# Keyboard.net
KiCad netlist of a schematic drawn in Altium Designer
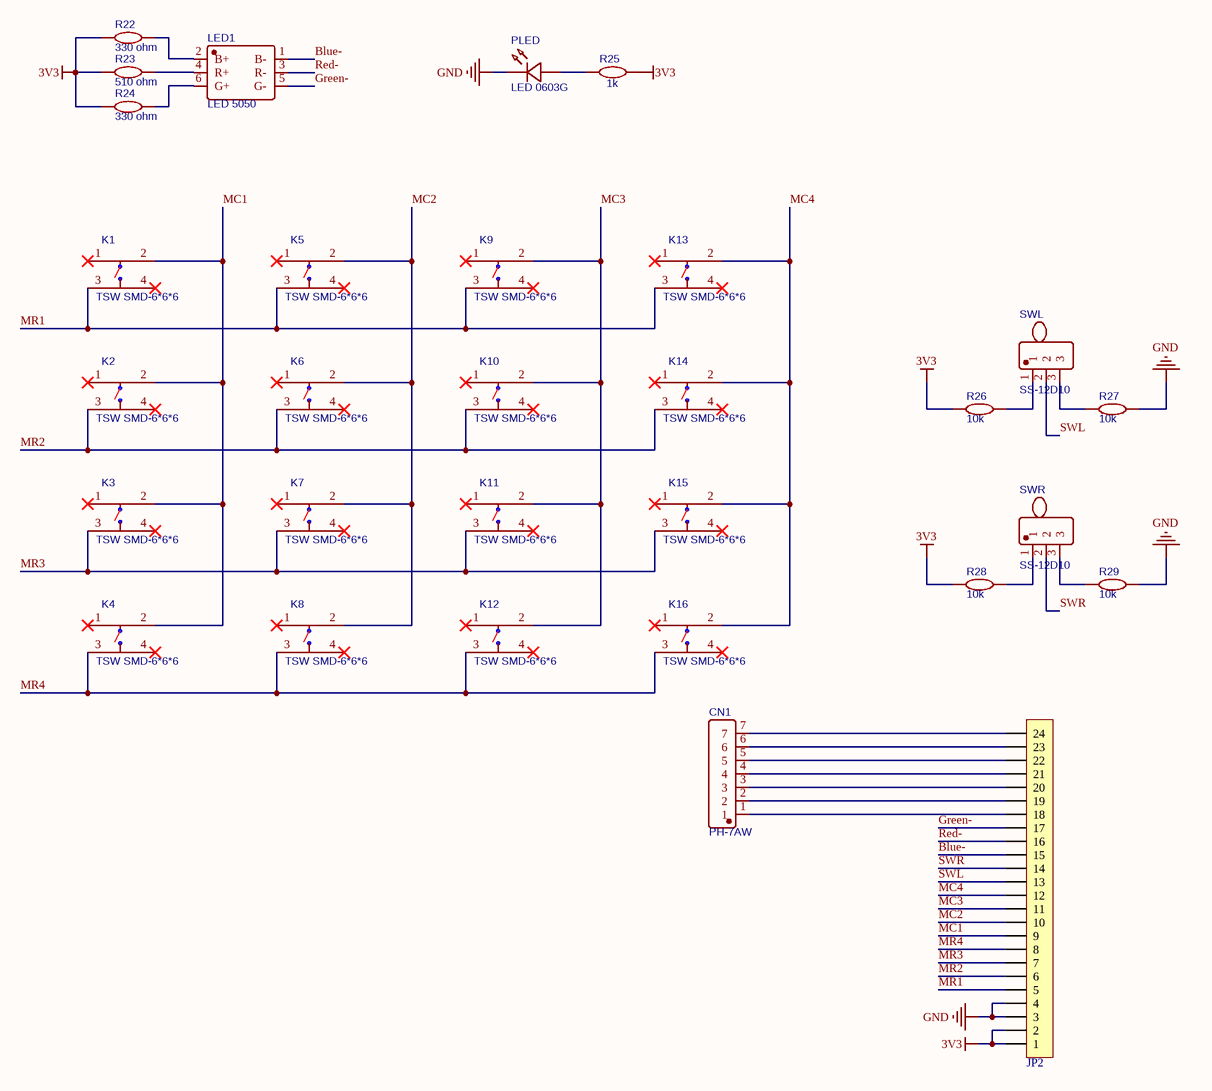
[diagram p0: Keyboard.SchDoc]

(export (version "E")
  (design (tool "Eeschema 10.0.6"))
  (components
    (comp (ref "CN1")
      (value "PH-7AW")
      (footprint "CONN-TH_PH-7AW")
      (fields (field (name "BOM_SUPPLIER PART") "C722789") (field (name "CONTRIBUTOR") "LCSC"))
      (libsource (lib "PH2.0_schlib") (part "PH-7AW"))
    )
    (comp (ref "JP2")
      (value "FPC1.0-24P")
      (footprint "FPC1.0-2H-WS-24P")
      (description "FPC连接器")
      (fields (field (name "版权归属") "黎明电子style"))
      (libsource (lib "FPC_schlib") (part "FPC-24P-1.0"))
    )
    (comp (ref "K1")
      (value "TSW SMD-6*6*6")
      (footprint "TSW SMD-6*6*6")
      (fields
        (field (name "BOM_SUPPLIER PART") "C231715")
        (field (name "BOM_MANUFACTURER PART") "KAN0661-1001B")
        (field (name "CONTRIBUTOR") "LCSC")
      )
      (libsource (lib "Button_schlib") (part "TSW SMD-6*6*6"))
    )
    (comp (ref "K2")
      (value "TSW SMD-6*6*6")
      (footprint "TSW SMD-6*6*6")
      (fields
        (field (name "BOM_SUPPLIER PART") "C231715")
        (field (name "BOM_MANUFACTURER PART") "KAN0661-1001B")
        (field (name "CONTRIBUTOR") "LCSC")
      )
      (libsource (lib "Button_schlib") (part "TSW SMD-6*6*6"))
    )
    (comp (ref "K3")
      (value "TSW SMD-6*6*6")
      (footprint "TSW SMD-6*6*6")
      (fields
        (field (name "BOM_SUPPLIER PART") "C231715")
        (field (name "BOM_MANUFACTURER PART") "KAN0661-1001B")
        (field (name "CONTRIBUTOR") "LCSC")
      )
      (libsource (lib "Button_schlib") (part "TSW SMD-6*6*6"))
    )
    (comp (ref "K4")
      (value "TSW SMD-6*6*6")
      (footprint "TSW SMD-6*6*6")
      (fields
        (field (name "BOM_SUPPLIER PART") "C231715")
        (field (name "BOM_MANUFACTURER PART") "KAN0661-1001B")
        (field (name "CONTRIBUTOR") "LCSC")
      )
      (libsource (lib "Button_schlib") (part "TSW SMD-6*6*6"))
    )
    (comp (ref "K5")
      (value "TSW SMD-6*6*6")
      (footprint "TSW SMD-6*6*6")
      (fields
        (field (name "BOM_SUPPLIER PART") "C231715")
        (field (name "BOM_MANUFACTURER PART") "KAN0661-1001B")
        (field (name "CONTRIBUTOR") "LCSC")
      )
      (libsource (lib "Button_schlib") (part "TSW SMD-6*6*6"))
    )
    (comp (ref "K6")
      (value "TSW SMD-6*6*6")
      (footprint "TSW SMD-6*6*6")
      (fields
        (field (name "BOM_SUPPLIER PART") "C231715")
        (field (name "BOM_MANUFACTURER PART") "KAN0661-1001B")
        (field (name "CONTRIBUTOR") "LCSC")
      )
      (libsource (lib "Button_schlib") (part "TSW SMD-6*6*6"))
    )
    (comp (ref "K7")
      (value "TSW SMD-6*6*6")
      (footprint "TSW SMD-6*6*6")
      (fields
        (field (name "BOM_SUPPLIER PART") "C231715")
        (field (name "BOM_MANUFACTURER PART") "KAN0661-1001B")
        (field (name "CONTRIBUTOR") "LCSC")
      )
      (libsource (lib "Button_schlib") (part "TSW SMD-6*6*6"))
    )
    (comp (ref "K8")
      (value "TSW SMD-6*6*6")
      (footprint "TSW SMD-6*6*6")
      (fields
        (field (name "BOM_SUPPLIER PART") "C231715")
        (field (name "BOM_MANUFACTURER PART") "KAN0661-1001B")
        (field (name "CONTRIBUTOR") "LCSC")
      )
      (libsource (lib "Button_schlib") (part "TSW SMD-6*6*6"))
    )
    (comp (ref "K9")
      (value "TSW SMD-6*6*6")
      (footprint "TSW SMD-6*6*6")
      (fields
        (field (name "BOM_SUPPLIER PART") "C231715")
        (field (name "BOM_MANUFACTURER PART") "KAN0661-1001B")
        (field (name "CONTRIBUTOR") "LCSC")
      )
      (libsource (lib "Button_schlib") (part "TSW SMD-6*6*6"))
    )
    (comp (ref "K10")
      (value "TSW SMD-6*6*6")
      (footprint "TSW SMD-6*6*6")
      (fields
        (field (name "BOM_SUPPLIER PART") "C231715")
        (field (name "BOM_MANUFACTURER PART") "KAN0661-1001B")
        (field (name "CONTRIBUTOR") "LCSC")
      )
      (libsource (lib "Button_schlib") (part "TSW SMD-6*6*6"))
    )
    (comp (ref "K11")
      (value "TSW SMD-6*6*6")
      (footprint "TSW SMD-6*6*6")
      (fields
        (field (name "BOM_SUPPLIER PART") "C231715")
        (field (name "BOM_MANUFACTURER PART") "KAN0661-1001B")
        (field (name "CONTRIBUTOR") "LCSC")
      )
      (libsource (lib "Button_schlib") (part "TSW SMD-6*6*6"))
    )
    (comp (ref "K12")
      (value "TSW SMD-6*6*6")
      (footprint "TSW SMD-6*6*6")
      (fields
        (field (name "BOM_SUPPLIER PART") "C231715")
        (field (name "BOM_MANUFACTURER PART") "KAN0661-1001B")
        (field (name "CONTRIBUTOR") "LCSC")
      )
      (libsource (lib "Button_schlib") (part "TSW SMD-6*6*6"))
    )
    (comp (ref "K13")
      (value "TSW SMD-6*6*6")
      (footprint "TSW SMD-6*6*6")
      (fields
        (field (name "BOM_SUPPLIER PART") "C231715")
        (field (name "BOM_MANUFACTURER PART") "KAN0661-1001B")
        (field (name "CONTRIBUTOR") "LCSC")
      )
      (libsource (lib "Button_schlib") (part "TSW SMD-6*6*6"))
    )
    (comp (ref "K14")
      (value "TSW SMD-6*6*6")
      (footprint "TSW SMD-6*6*6")
      (fields
        (field (name "BOM_SUPPLIER PART") "C231715")
        (field (name "BOM_MANUFACTURER PART") "KAN0661-1001B")
        (field (name "CONTRIBUTOR") "LCSC")
      )
      (libsource (lib "Button_schlib") (part "TSW SMD-6*6*6"))
    )
    (comp (ref "K15")
      (value "TSW SMD-6*6*6")
      (footprint "TSW SMD-6*6*6")
      (fields
        (field (name "BOM_SUPPLIER PART") "C231715")
        (field (name "BOM_MANUFACTURER PART") "KAN0661-1001B")
        (field (name "CONTRIBUTOR") "LCSC")
      )
      (libsource (lib "Button_schlib") (part "TSW SMD-6*6*6"))
    )
    (comp (ref "K16")
      (value "TSW SMD-6*6*6")
      (footprint "TSW SMD-6*6*6")
      (fields
        (field (name "BOM_SUPPLIER PART") "C231715")
        (field (name "BOM_MANUFACTURER PART") "KAN0661-1001B")
        (field (name "CONTRIBUTOR") "LCSC")
      )
      (libsource (lib "Button_schlib") (part "TSW SMD-6*6*6"))
    )
    (comp (ref "LED1")
      (value "LED 5050")
      (footprint "LED 5050")
      (description "5050RGB-LED")
      (fields
        (field (name "BOM_SUPPLIER PART") "C3014404")
        (field (name "BOM_MANUFACTURER PART") "11-21/BHC-AQ2S2/2T")
        (field (name "CONTRIBUTOR") "lcsc")
      )
      (libsource (lib "LED_schlib") (part "LED 5050"))
    )
    (comp (ref "PLED")
      (value "LED 0603G")
      (footprint "LED 0603G")
      (description "绿色0603LED")
      (fields
        (field (name "BOM_SUPPLIER PART") "C3014404")
        (field (name "BOM_MANUFACTURER PART") "11-21/BHC-AQ2S2/2T")
        (field (name "CONTRIBUTOR") "lcsc")
      )
      (libsource (lib "LED_schlib") (part "LED 0603G"))
    )
    (comp (ref "R22")
      (value "330 ohm")
      (footprint "R0603")
      (fields
        (field (name "BOM_SUPPLIER PART") "C326890")
        (field (name "BOM_MANUFACTURER PART") "SR0603JR-071RL")
        (field (name "CONTRIBUTOR") "LCSC")
      )
      (libsource (lib "RC_schlib") (part "R0603"))
    )
    (comp (ref "R23")
      (value "510 ohm")
      (footprint "R0603")
      (fields
        (field (name "BOM_SUPPLIER PART") "C326890")
        (field (name "BOM_MANUFACTURER PART") "SR0603JR-071RL")
        (field (name "CONTRIBUTOR") "LCSC")
      )
      (libsource (lib "RC_schlib") (part "R0603"))
    )
    (comp (ref "R24")
      (value "330 ohm")
      (footprint "R0603")
      (fields
        (field (name "BOM_SUPPLIER PART") "C326890")
        (field (name "BOM_MANUFACTURER PART") "SR0603JR-071RL")
        (field (name "CONTRIBUTOR") "LCSC")
      )
      (libsource (lib "RC_schlib") (part "R0603"))
    )
    (comp (ref "R25")
      (value "1k")
      (footprint "R0603")
      (fields
        (field (name "BOM_SUPPLIER PART") "C326890")
        (field (name "BOM_MANUFACTURER PART") "SR0603JR-071RL")
        (field (name "CONTRIBUTOR") "LCSC")
      )
      (libsource (lib "RC_schlib") (part "R0603"))
    )
    (comp (ref "R26")
      (value "10k")
      (footprint "R0603")
      (fields
        (field (name "BOM_SUPPLIER PART") "C326890")
        (field (name "BOM_MANUFACTURER PART") "SR0603JR-071RL")
        (field (name "CONTRIBUTOR") "LCSC")
      )
      (libsource (lib "RC_schlib") (part "R0603"))
    )
    (comp (ref "R27")
      (value "10k")
      (footprint "R0603")
      (fields
        (field (name "BOM_SUPPLIER PART") "C326890")
        (field (name "BOM_MANUFACTURER PART") "SR0603JR-071RL")
        (field (name "CONTRIBUTOR") "LCSC")
      )
      (libsource (lib "RC_schlib") (part "R0603"))
    )
    (comp (ref "R28")
      (value "10k")
      (footprint "R0603")
      (fields
        (field (name "BOM_SUPPLIER PART") "C326890")
        (field (name "BOM_MANUFACTURER PART") "SR0603JR-071RL")
        (field (name "CONTRIBUTOR") "LCSC")
      )
      (libsource (lib "RC_schlib") (part "R0603"))
    )
    (comp (ref "R29")
      (value "10k")
      (footprint "R0603")
      (fields
        (field (name "BOM_SUPPLIER PART") "C326890")
        (field (name "BOM_MANUFACTURER PART") "SR0603JR-071RL")
        (field (name "CONTRIBUTOR") "LCSC")
      )
      (libsource (lib "RC_schlib") (part "R0603"))
    )
    (comp (ref "SWL")
      (value "SS-12D10")
      (footprint "SS-12D10")
      (description "立式三脚拨动开关")
      (fields
        (field (name "BOM_SUPPLIER PART") "C496154")
        (field (name "BOM_MANUFACTURER PART") "1MS1T1B1M1QES-5")
        (field (name "CONTRIBUTOR") "LCSC")
      )
      (libsource (lib "Switch_schlib") (part "SS-12D10"))
    )
    (comp (ref "SWR")
      (value "SS-12D10")
      (footprint "SS-12D10")
      (description "立式三脚拨动开关")
      (fields
        (field (name "BOM_SUPPLIER PART") "C496154")
        (field (name "BOM_MANUFACTURER PART") "1MS1T1B1M1QES-5")
        (field (name "CONTRIBUTOR") "LCSC")
      )
      (libsource (lib "Switch_schlib") (part "SS-12D10"))
    )
  )
  (nets
    (net (code "1") (name "/Blue-") (class "Default")
      (node (ref "JP2") (pin "15") (pinfunction "15_15") (pintype "passive"))
      (node (ref "LED1") (pin "1") (pinfunction "B-_1") (pintype "passive"))
    )
    (net (code "2") (name "/Green-") (class "Default")
      (node (ref "JP2") (pin "17") (pinfunction "17_17") (pintype "passive"))
      (node (ref "LED1") (pin "5") (pinfunction "G-_5") (pintype "passive"))
    )
    (net (code "3") (name "/MC1") (class "Default")
      (node (ref "JP2") (pin "9") (pinfunction "9_9") (pintype "passive"))
      (node (ref "K1") (pin "2") (pinfunction "2_2") (pintype "passive"))
      (node (ref "K2") (pin "2") (pinfunction "2_2") (pintype "passive"))
      (node (ref "K3") (pin "2") (pinfunction "2_2") (pintype "passive"))
      (node (ref "K4") (pin "2") (pinfunction "2_2") (pintype "passive"))
    )
    (net (code "4") (name "/MC2") (class "Default")
      (node (ref "JP2") (pin "10") (pinfunction "10_10") (pintype "passive"))
      (node (ref "K5") (pin "2") (pinfunction "2_2") (pintype "passive"))
      (node (ref "K6") (pin "2") (pinfunction "2_2") (pintype "passive"))
      (node (ref "K7") (pin "2") (pinfunction "2_2") (pintype "passive"))
      (node (ref "K8") (pin "2") (pinfunction "2_2") (pintype "passive"))
    )
    (net (code "5") (name "/MC3") (class "Default")
      (node (ref "JP2") (pin "11") (pinfunction "11_11") (pintype "passive"))
      (node (ref "K10") (pin "2") (pinfunction "2_2") (pintype "passive"))
      (node (ref "K11") (pin "2") (pinfunction "2_2") (pintype "passive"))
      (node (ref "K12") (pin "2") (pinfunction "2_2") (pintype "passive"))
      (node (ref "K9") (pin "2") (pinfunction "2_2") (pintype "passive"))
    )
    (net (code "6") (name "/MC4") (class "Default")
      (node (ref "JP2") (pin "12") (pinfunction "12_12") (pintype "passive"))
      (node (ref "K13") (pin "2") (pinfunction "2_2") (pintype "passive"))
      (node (ref "K14") (pin "2") (pinfunction "2_2") (pintype "passive"))
      (node (ref "K15") (pin "2") (pinfunction "2_2") (pintype "passive"))
      (node (ref "K16") (pin "2") (pinfunction "2_2") (pintype "passive"))
    )
    (net (code "7") (name "/MR1") (class "Default")
      (node (ref "JP2") (pin "5") (pinfunction "5_5") (pintype "passive"))
      (node (ref "K1") (pin "3") (pinfunction "3_3") (pintype "passive"))
      (node (ref "K13") (pin "3") (pinfunction "3_3") (pintype "passive"))
      (node (ref "K5") (pin "3") (pinfunction "3_3") (pintype "passive"))
      (node (ref "K9") (pin "3") (pinfunction "3_3") (pintype "passive"))
    )
    (net (code "8") (name "/MR2") (class "Default")
      (node (ref "JP2") (pin "6") (pinfunction "6_6") (pintype "passive"))
      (node (ref "K10") (pin "3") (pinfunction "3_3") (pintype "passive"))
      (node (ref "K14") (pin "3") (pinfunction "3_3") (pintype "passive"))
      (node (ref "K2") (pin "3") (pinfunction "3_3") (pintype "passive"))
      (node (ref "K6") (pin "3") (pinfunction "3_3") (pintype "passive"))
    )
    (net (code "9") (name "/MR3") (class "Default")
      (node (ref "JP2") (pin "7") (pinfunction "7_7") (pintype "passive"))
      (node (ref "K11") (pin "3") (pinfunction "3_3") (pintype "passive"))
      (node (ref "K15") (pin "3") (pinfunction "3_3") (pintype "passive"))
      (node (ref "K3") (pin "3") (pinfunction "3_3") (pintype "passive"))
      (node (ref "K7") (pin "3") (pinfunction "3_3") (pintype "passive"))
    )
    (net (code "10") (name "/MR4") (class "Default")
      (node (ref "JP2") (pin "8") (pinfunction "8_8") (pintype "passive"))
      (node (ref "K12") (pin "3") (pinfunction "3_3") (pintype "passive"))
      (node (ref "K16") (pin "3") (pinfunction "3_3") (pintype "passive"))
      (node (ref "K4") (pin "3") (pinfunction "3_3") (pintype "passive"))
      (node (ref "K8") (pin "3") (pinfunction "3_3") (pintype "passive"))
    )
    (net (code "11") (name "/Red-") (class "Default")
      (node (ref "JP2") (pin "16") (pinfunction "16_16") (pintype "passive"))
      (node (ref "LED1") (pin "3") (pinfunction "R-_3") (pintype "passive"))
    )
    (net (code "12") (name "/SWL") (class "Default")
      (node (ref "JP2") (pin "13") (pinfunction "13_13") (pintype "passive"))
      (node (ref "SWL") (pin "2") (pinfunction "2_2") (pintype "passive"))
    )
    (net (code "13") (name "/SWR") (class "Default")
      (node (ref "JP2") (pin "14") (pinfunction "14_14") (pintype "passive"))
      (node (ref "SWR") (pin "2") (pinfunction "2_2") (pintype "passive"))
    )
    (net (code "14") (name "3V3") (class "Default")
      (node (ref "JP2") (pin "1") (pinfunction "1_1") (pintype "passive"))
      (node (ref "JP2") (pin "2") (pinfunction "2_2") (pintype "passive"))
      (node (ref "R22") (pin "2") (pinfunction "2_2") (pintype "passive"))
      (node (ref "R23") (pin "2") (pinfunction "2_2") (pintype "passive"))
      (node (ref "R24") (pin "2") (pinfunction "2_2") (pintype "passive"))
      (node (ref "R25") (pin "1") (pinfunction "1_1") (pintype "passive"))
      (node (ref "R26") (pin "1") (pinfunction "1_1") (pintype "passive"))
      (node (ref "R28") (pin "1") (pinfunction "1_1") (pintype "passive"))
    )
    (net (code "15") (name "GND") (class "Default")
      (node (ref "JP2") (pin "3") (pinfunction "3_3") (pintype "passive"))
      (node (ref "JP2") (pin "4") (pinfunction "4_4") (pintype "passive"))
      (node (ref "PLED") (pin "2") (pinfunction "K_2") (pintype "passive"))
      (node (ref "R27") (pin "2") (pinfunction "2_2") (pintype "passive"))
      (node (ref "R29") (pin "2") (pinfunction "2_2") (pintype "passive"))
    )
    (net (code "16") (name "Net-(CN1-Pad1)") (class "Default")
      (node (ref "CN1") (pin "1") (pinfunction "1_1") (pintype "passive"))
      (node (ref "JP2") (pin "18") (pinfunction "18_18") (pintype "passive"))
    )
    (net (code "17") (name "Net-(CN1-Pad2)") (class "Default")
      (node (ref "CN1") (pin "2") (pinfunction "2_2") (pintype "passive"))
      (node (ref "JP2") (pin "19") (pinfunction "19_19") (pintype "passive"))
    )
    (net (code "18") (name "Net-(CN1-Pad3)") (class "Default")
      (node (ref "CN1") (pin "3") (pinfunction "3_3") (pintype "passive"))
      (node (ref "JP2") (pin "20") (pinfunction "20_20") (pintype "passive"))
    )
    (net (code "19") (name "Net-(CN1-Pad4)") (class "Default")
      (node (ref "CN1") (pin "4") (pinfunction "4_4") (pintype "passive"))
      (node (ref "JP2") (pin "21") (pinfunction "21_21") (pintype "passive"))
    )
    (net (code "20") (name "Net-(CN1-Pad5)") (class "Default")
      (node (ref "CN1") (pin "5") (pinfunction "5_5") (pintype "passive"))
      (node (ref "JP2") (pin "22") (pinfunction "22_22") (pintype "passive"))
    )
    (net (code "21") (name "Net-(CN1-Pad6)") (class "Default")
      (node (ref "CN1") (pin "6") (pinfunction "6_6") (pintype "passive"))
      (node (ref "JP2") (pin "23") (pinfunction "23_23") (pintype "passive"))
    )
    (net (code "22") (name "Net-(CN1-Pad7)") (class "Default")
      (node (ref "CN1") (pin "7") (pinfunction "7_7") (pintype "passive"))
      (node (ref "JP2") (pin "24") (pinfunction "24_24") (pintype "passive"))
    )
    (net (code "23") (name "Net-(LED1-B+)") (class "Default")
      (node (ref "LED1") (pin "2") (pinfunction "B+_2") (pintype "passive"))
      (node (ref "R22") (pin "1") (pinfunction "1_1") (pintype "passive"))
    )
    (net (code "24") (name "Net-(LED1-G+)") (class "Default")
      (node (ref "LED1") (pin "6") (pinfunction "G+_6") (pintype "passive"))
      (node (ref "R24") (pin "1") (pinfunction "1_1") (pintype "passive"))
    )
    (net (code "25") (name "Net-(LED1-R+)") (class "Default")
      (node (ref "LED1") (pin "4") (pinfunction "R+_4") (pintype "passive"))
      (node (ref "R23") (pin "1") (pinfunction "1_1") (pintype "passive"))
    )
    (net (code "26") (name "Net-(PLED-A)") (class "Default")
      (node (ref "PLED") (pin "1") (pinfunction "A_1") (pintype "passive"))
      (node (ref "R25") (pin "2") (pinfunction "2_2") (pintype "passive"))
    )
    (net (code "27") (name "Net-(R26-Pad2)") (class "Default")
      (node (ref "R26") (pin "2") (pinfunction "2_2") (pintype "passive"))
      (node (ref "SWL") (pin "1") (pinfunction "1_1") (pintype "passive"))
    )
    (net (code "28") (name "Net-(R27-Pad1)") (class "Default")
      (node (ref "R27") (pin "1") (pinfunction "1_1") (pintype "passive"))
      (node (ref "SWL") (pin "3") (pinfunction "3_3") (pintype "passive"))
    )
    (net (code "29") (name "Net-(R28-Pad2)") (class "Default")
      (node (ref "R28") (pin "2") (pinfunction "2_2") (pintype "passive"))
      (node (ref "SWR") (pin "1") (pinfunction "1_1") (pintype "passive"))
    )
    (net (code "30") (name "Net-(R29-Pad1)") (class "Default")
      (node (ref "R29") (pin "1") (pinfunction "1_1") (pintype "passive"))
      (node (ref "SWR") (pin "3") (pinfunction "3_3") (pintype "passive"))
    )
    (net (code "31") (name "unconnected-(K1-Pad1)") (class "Default")
      (node (ref "K1") (pin "1") (pinfunction "1_1") (pintype "passive+no_connect"))
    )
    (net (code "32") (name "unconnected-(K1-Pad4)") (class "Default")
      (node (ref "K1") (pin "4") (pinfunction "4_4") (pintype "passive+no_connect"))
    )
    (net (code "33") (name "unconnected-(K2-Pad1)") (class "Default")
      (node (ref "K2") (pin "1") (pinfunction "1_1") (pintype "passive+no_connect"))
    )
    (net (code "34") (name "unconnected-(K2-Pad4)") (class "Default")
      (node (ref "K2") (pin "4") (pinfunction "4_4") (pintype "passive+no_connect"))
    )
    (net (code "35") (name "unconnected-(K3-Pad1)") (class "Default")
      (node (ref "K3") (pin "1") (pinfunction "1_1") (pintype "passive+no_connect"))
    )
    (net (code "36") (name "unconnected-(K3-Pad4)") (class "Default")
      (node (ref "K3") (pin "4") (pinfunction "4_4") (pintype "passive+no_connect"))
    )
    (net (code "37") (name "unconnected-(K4-Pad1)") (class "Default")
      (node (ref "K4") (pin "1") (pinfunction "1_1") (pintype "passive+no_connect"))
    )
    (net (code "38") (name "unconnected-(K4-Pad4)") (class "Default")
      (node (ref "K4") (pin "4") (pinfunction "4_4") (pintype "passive+no_connect"))
    )
    (net (code "39") (name "unconnected-(K5-Pad1)") (class "Default")
      (node (ref "K5") (pin "1") (pinfunction "1_1") (pintype "passive+no_connect"))
    )
    (net (code "40") (name "unconnected-(K5-Pad4)") (class "Default")
      (node (ref "K5") (pin "4") (pinfunction "4_4") (pintype "passive+no_connect"))
    )
    (net (code "41") (name "unconnected-(K6-Pad1)") (class "Default")
      (node (ref "K6") (pin "1") (pinfunction "1_1") (pintype "passive+no_connect"))
    )
    (net (code "42") (name "unconnected-(K6-Pad4)") (class "Default")
      (node (ref "K6") (pin "4") (pinfunction "4_4") (pintype "passive+no_connect"))
    )
    (net (code "43") (name "unconnected-(K7-Pad1)") (class "Default")
      (node (ref "K7") (pin "1") (pinfunction "1_1") (pintype "passive+no_connect"))
    )
    (net (code "44") (name "unconnected-(K7-Pad4)") (class "Default")
      (node (ref "K7") (pin "4") (pinfunction "4_4") (pintype "passive+no_connect"))
    )
    (net (code "45") (name "unconnected-(K8-Pad1)") (class "Default")
      (node (ref "K8") (pin "1") (pinfunction "1_1") (pintype "passive+no_connect"))
    )
    (net (code "46") (name "unconnected-(K8-Pad4)") (class "Default")
      (node (ref "K8") (pin "4") (pinfunction "4_4") (pintype "passive+no_connect"))
    )
    (net (code "47") (name "unconnected-(K9-Pad1)") (class "Default")
      (node (ref "K9") (pin "1") (pinfunction "1_1") (pintype "passive+no_connect"))
    )
    (net (code "48") (name "unconnected-(K9-Pad4)") (class "Default")
      (node (ref "K9") (pin "4") (pinfunction "4_4") (pintype "passive+no_connect"))
    )
    (net (code "49") (name "unconnected-(K10-Pad1)") (class "Default")
      (node (ref "K10") (pin "1") (pinfunction "1_1") (pintype "passive+no_connect"))
    )
    (net (code "50") (name "unconnected-(K10-Pad4)") (class "Default")
      (node (ref "K10") (pin "4") (pinfunction "4_4") (pintype "passive+no_connect"))
    )
    (net (code "51") (name "unconnected-(K11-Pad1)") (class "Default")
      (node (ref "K11") (pin "1") (pinfunction "1_1") (pintype "passive+no_connect"))
    )
    (net (code "52") (name "unconnected-(K11-Pad4)") (class "Default")
      (node (ref "K11") (pin "4") (pinfunction "4_4") (pintype "passive+no_connect"))
    )
    (net (code "53") (name "unconnected-(K12-Pad1)") (class "Default")
      (node (ref "K12") (pin "1") (pinfunction "1_1") (pintype "passive+no_connect"))
    )
    (net (code "54") (name "unconnected-(K12-Pad4)") (class "Default")
      (node (ref "K12") (pin "4") (pinfunction "4_4") (pintype "passive+no_connect"))
    )
    (net (code "55") (name "unconnected-(K13-Pad1)") (class "Default")
      (node (ref "K13") (pin "1") (pinfunction "1_1") (pintype "passive+no_connect"))
    )
    (net (code "56") (name "unconnected-(K13-Pad4)") (class "Default")
      (node (ref "K13") (pin "4") (pinfunction "4_4") (pintype "passive+no_connect"))
    )
    (net (code "57") (name "unconnected-(K14-Pad1)") (class "Default")
      (node (ref "K14") (pin "1") (pinfunction "1_1") (pintype "passive+no_connect"))
    )
    (net (code "58") (name "unconnected-(K14-Pad4)") (class "Default")
      (node (ref "K14") (pin "4") (pinfunction "4_4") (pintype "passive+no_connect"))
    )
    (net (code "59") (name "unconnected-(K15-Pad1)") (class "Default")
      (node (ref "K15") (pin "1") (pinfunction "1_1") (pintype "passive+no_connect"))
    )
    (net (code "60") (name "unconnected-(K15-Pad4)") (class "Default")
      (node (ref "K15") (pin "4") (pinfunction "4_4") (pintype "passive+no_connect"))
    )
    (net (code "61") (name "unconnected-(K16-Pad1)") (class "Default")
      (node (ref "K16") (pin "1") (pinfunction "1_1") (pintype "passive+no_connect"))
    )
    (net (code "62") (name "unconnected-(K16-Pad4)") (class "Default")
      (node (ref "K16") (pin "4") (pinfunction "4_4") (pintype "passive+no_connect"))
    )
  )
)
